# power.net
KiCad netlist of a schematic drawn in Altium Designer
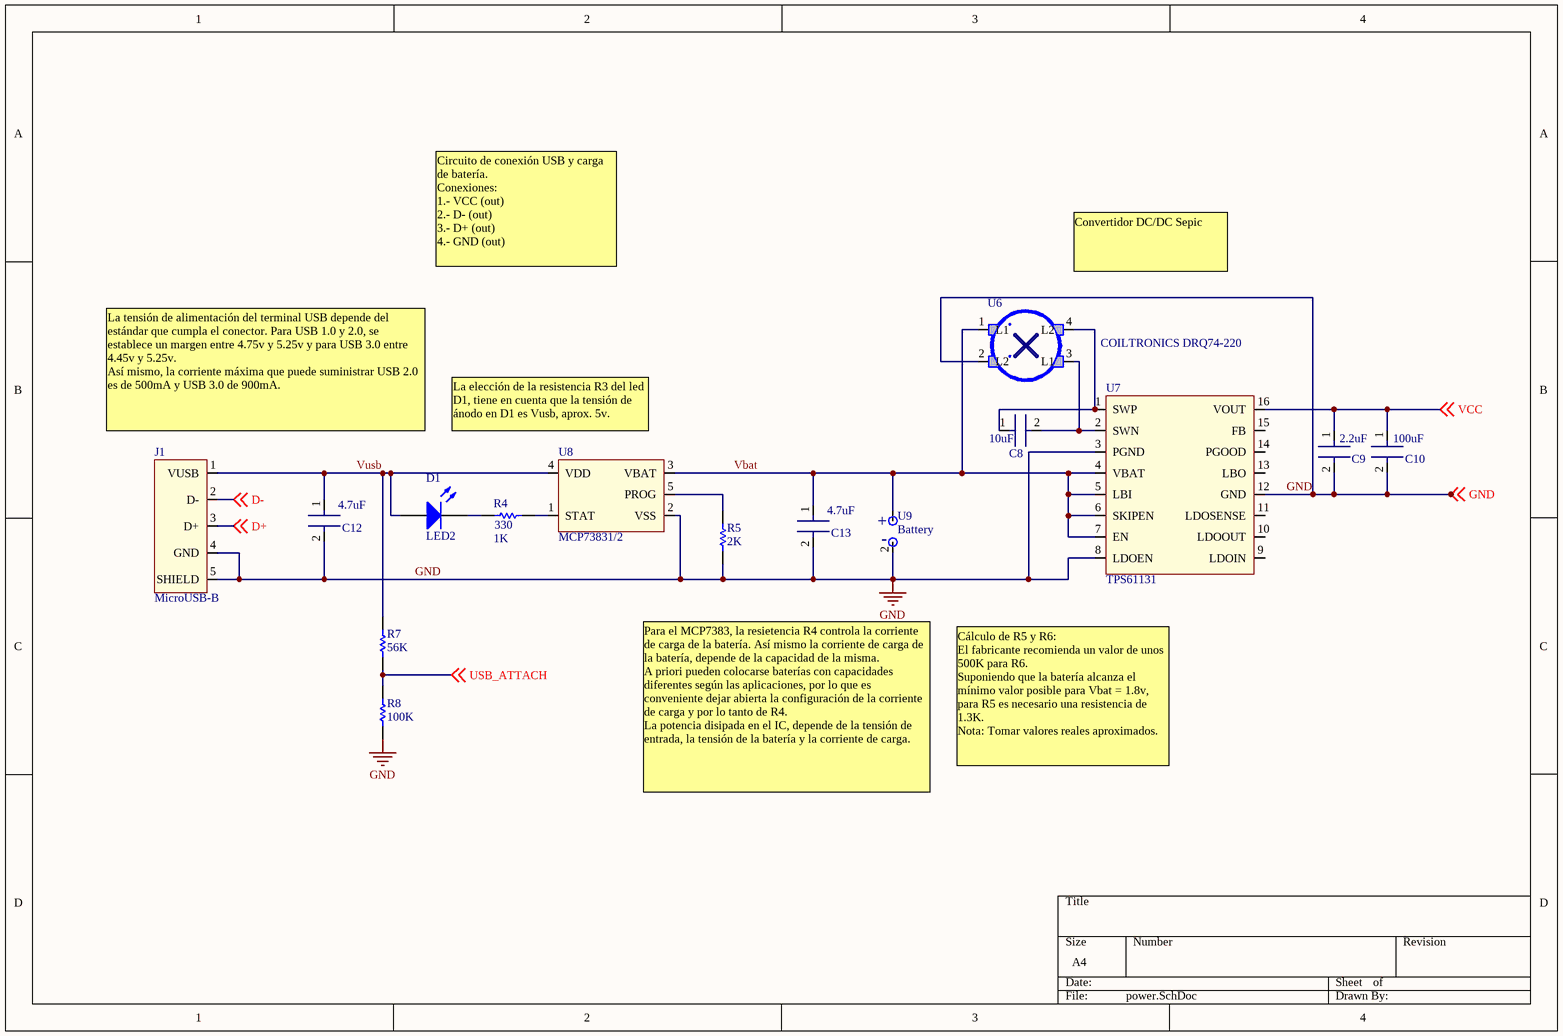
[diagram p0: power.SchDoc]

(export (version "E")
  (design (tool "Eeschema 10.0.6"))
  (components
    (comp (ref "C8") (value "10uF") (footprint "C1206") (libsource (lib "uMote") (part "TDK C3216X7R1C106K")))
    (comp (ref "C9")
      (value "2.2uF")
      (footprint "C1206")
      (libsource (lib "uMote") (part "TDK C3216X7R1C106K"))
    )
    (comp (ref "C10")
      (value "100uF")
      (footprint "C1206")
      (libsource (lib "uMote") (part "TDK C3216X7R1C106K"))
    )
    (comp (ref "C12")
      (value "4.7uF")
      (footprint "C1206")
      (libsource (lib "uMote") (part "TDK C3216X7R1C106K"))
    )
    (comp (ref "C13")
      (value "4.7uF")
      (footprint "C1206")
      (libsource (lib "uMote") (part "TDK C3216X7R1C106K"))
    )
    (comp (ref "D1")
      (value "LED2")
      (footprint "LED SMD 1206")
      (description "Typical RED, GREEN, YELLOW, AMBER GaAs LED")
      (fields (field (name "PUBLISHER") "Altium Limited"))
      (libsource (lib "Miscellaneous Devices") (part "LED2"))
    )
    (comp (ref "J1")
      (value "MicroUSB-B")
      (footprint "Micro USB Tipo B")
      (libsource (lib "uMote") (part "MicroUSB-B"))
    )
    (comp (ref "R4")
      (value "330")
      (footprint "3216[1206]")
      (description "Semiconductor Resistor")
      (fields (field (name "ALTIUM_VALUE") "1K") (field (name "PUBLISHER") "Altium Limited"))
      (libsource (lib "Miscellaneous Devices") (part "Res Semi"))
    )
    (comp (ref "R5")
      (value "2K")
      (footprint "3216[1206]")
      (description "Semiconductor Resistor")
      (fields (field (name "PUBLISHER") "Altium Limited"))
      (libsource (lib "Miscellaneous Devices") (part "Res Semi"))
    )
    (comp (ref "R7")
      (value "56K")
      (footprint "3216[1206]")
      (description "Semiconductor Resistor")
      (fields (field (name "PUBLISHER") "Altium Limited"))
      (libsource (lib "Miscellaneous Devices") (part "Res Semi"))
    )
    (comp (ref "R8")
      (value "100K")
      (footprint "3216[1206]")
      (description "Semiconductor Resistor")
      (fields (field (name "PUBLISHER") "Altium Limited"))
      (libsource (lib "Miscellaneous Devices") (part "Res Semi"))
    )
    (comp (ref "U6")
      (value "COILTRONICS DRQ74-220")
      (footprint "Trafo Flyback-SEPIC - soldadura manual")
      (libsource (lib "uMote") (part "COILTRONICS DRQ74-220"))
    )
    (comp (ref "U7") (value "TPS61131") (footprint "TPS61131") (libsource (lib "uMote") (part "TPS61131")))
    (comp (ref "U8")
      (value "MCP73831/2")
      (footprint "MCP73831")
      (libsource (lib "uMote") (part "MCP73831/2"))
    )
    (comp (ref "U9") (value "Battery") (footprint "JST PH") (libsource (lib "uMote") (part "Battery")))
  )
  (nets
    (net (code "1") (name "/Vbat") (class "Default")
      (node (ref "C13") (pin "1") (pinfunction "1_1") (pintype "passive"))
      (node (ref "U6") (pin "1") (pinfunction "L1_1") (pintype "passive"))
      (node (ref "U7") (pin "4") (pinfunction "VBAT_4") (pintype "passive"))
      (node (ref "U7") (pin "5") (pinfunction "LBI_5") (pintype "passive"))
      (node (ref "U7") (pin "6") (pinfunction "SKIPEN_6") (pintype "passive"))
      (node (ref "U7") (pin "7") (pinfunction "EN_7") (pintype "passive"))
      (node (ref "U8") (pin "3") (pinfunction "VBAT_3") (pintype "passive"))
      (node (ref "U9") (pin "1") (pintype "passive"))
    )
    (net (code "2") (name "/Vusb") (class "Default")
      (node (ref "C12") (pin "1") (pinfunction "1_1") (pintype "passive"))
      (node (ref "D1") (pin "1") (pinfunction "A_1") (pintype "passive"))
      (node (ref "J1") (pin "1") (pinfunction "VUSB_1") (pintype "passive"))
      (node (ref "R7") (pin "2") (pinfunction "2_2") (pintype "passive"))
      (node (ref "U8") (pin "4") (pinfunction "VDD_4") (pintype "passive"))
    )
    (net (code "3") (name "D+") (class "Default")
      (node (ref "J1") (pin "3") (pinfunction "D+_3") (pintype "passive"))
    )
    (net (code "4") (name "D-") (class "Default")
      (node (ref "J1") (pin "2") (pinfunction "D-_2") (pintype "passive"))
    )
    (net (code "5") (name "GND") (class "Default")
      (node (ref "C10") (pin "2") (pinfunction "2_2") (pintype "passive"))
      (node (ref "C12") (pin "2") (pinfunction "2_2") (pintype "passive"))
      (node (ref "C13") (pin "2") (pinfunction "2_2") (pintype "passive"))
      (node (ref "C9") (pin "2") (pinfunction "2_2") (pintype "passive"))
      (node (ref "J1") (pin "4") (pinfunction "GND_4") (pintype "passive"))
      (node (ref "J1") (pin "5") (pinfunction "SHIELD_5") (pintype "passive"))
      (node (ref "R5") (pin "1") (pinfunction "1_1") (pintype "passive"))
      (node (ref "R8") (pin "1") (pinfunction "1_1") (pintype "passive"))
      (node (ref "U6") (pin "2") (pinfunction "L2_2") (pintype "passive"))
      (node (ref "U7") (pin "12") (pinfunction "GND_12") (pintype "passive"))
      (node (ref "U7") (pin "3") (pinfunction "PGND_3") (pintype "passive"))
      (node (ref "U7") (pin "8") (pinfunction "LDOEN_8") (pintype "passive"))
      (node (ref "U8") (pin "2") (pinfunction "VSS_2") (pintype "passive"))
      (node (ref "U9") (pin "2") (pintype "passive"))
    )
    (net (code "6") (name "Net-(D1-K)") (class "Default")
      (node (ref "D1") (pin "2") (pinfunction "K_2") (pintype "passive"))
      (node (ref "R4") (pin "1") (pinfunction "1_1") (pintype "passive"))
    )
    (net (code "7") (name "Net-(U7-SWN)") (class "Default")
      (node (ref "C8") (pin "2") (pinfunction "2_2") (pintype "passive"))
      (node (ref "U6") (pin "3") (pinfunction "L1_3") (pintype "passive"))
      (node (ref "U7") (pin "2") (pinfunction "SWN_2") (pintype "passive"))
    )
    (net (code "8") (name "Net-(U7-SWP)") (class "Default")
      (node (ref "C8") (pin "1") (pinfunction "1_1") (pintype "passive"))
      (node (ref "U6") (pin "4") (pinfunction "L2_4") (pintype "passive"))
      (node (ref "U7") (pin "1") (pinfunction "SWP_1") (pintype "passive"))
    )
    (net (code "9") (name "Net-(U8-PROG)") (class "Default")
      (node (ref "R5") (pin "2") (pinfunction "2_2") (pintype "passive"))
      (node (ref "U8") (pin "5") (pinfunction "PROG_5") (pintype "passive"))
    )
    (net (code "10") (name "Net-(U8-STAT)") (class "Default")
      (node (ref "R4") (pin "2") (pinfunction "2_2") (pintype "passive"))
      (node (ref "U8") (pin "1") (pinfunction "STAT_1") (pintype "passive"))
    )
    (net (code "11") (name "USB_ATTACH") (class "Default")
      (node (ref "R7") (pin "1") (pinfunction "1_1") (pintype "passive"))
      (node (ref "R8") (pin "2") (pinfunction "2_2") (pintype "passive"))
    )
    (net (code "12") (name "VCC") (class "Default")
      (node (ref "C10") (pin "1") (pinfunction "1_1") (pintype "passive"))
      (node (ref "C9") (pin "1") (pinfunction "1_1") (pintype "passive"))
      (node (ref "U7") (pin "16") (pinfunction "VOUT_16") (pintype "passive"))
    )
    (net (code "13") (name "unconnected-(U7-FB-Pad15)") (class "Default")
      (node (ref "U7") (pin "15") (pinfunction "FB_15") (pintype "passive"))
    )
    (net (code "14") (name "unconnected-(U7-LBO-Pad13)") (class "Default")
      (node (ref "U7") (pin "13") (pinfunction "LBO_13") (pintype "passive"))
    )
    (net (code "15") (name "unconnected-(U7-LDOIN-Pad9)") (class "Default")
      (node (ref "U7") (pin "9") (pinfunction "LDOIN_9") (pintype "passive"))
    )
    (net (code "16") (name "unconnected-(U7-LDOOUT-Pad10)") (class "Default")
      (node (ref "U7") (pin "10") (pinfunction "LDOOUT_10") (pintype "passive"))
    )
    (net (code "17") (name "unconnected-(U7-LDOSENSE-Pad11)") (class "Default")
      (node (ref "U7") (pin "11") (pinfunction "LDOSENSE_11") (pintype "passive"))
    )
    (net (code "18") (name "unconnected-(U7-PGOOD-Pad14)") (class "Default")
      (node (ref "U7") (pin "14") (pinfunction "PGOOD_14") (pintype "passive"))
    )
  )
)
